# LDS5362BS_breakout.net
KiCad netlist of a schematic drawn in EAGLE
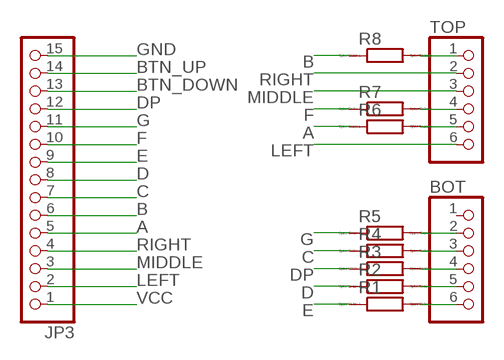
[diagram p0: schematic, sheet 1]

(export (version "E")
  (design (tool "Eeschema 10.0.6"))
  (components
    (comp (ref "BOT")
      (value "PINHD-1X6")
      (footprint "eagle-import:1X06")
      (libsource (lib "eagle-import") (part "PINHD-1X6"))
    )
    (comp (ref "JP3")
      (value "PINHD-1X15")
      (footprint "eagle-import:1X15")
      (libsource (lib "eagle-import") (part "PINHD-1X15"))
    )
    (comp (ref "R1")
      (value "R-EU_R1206")
      (footprint "eagle-import:R1206")
      (libsource (lib "eagle-import") (part "R-EU_R1206"))
    )
    (comp (ref "R2")
      (value "R-EU_R1206")
      (footprint "eagle-import:R1206")
      (libsource (lib "eagle-import") (part "R-EU_R1206"))
    )
    (comp (ref "R3")
      (value "R-EU_R1206")
      (footprint "eagle-import:R1206")
      (libsource (lib "eagle-import") (part "R-EU_R1206"))
    )
    (comp (ref "R4")
      (value "R-EU_R1206")
      (footprint "eagle-import:R1206")
      (libsource (lib "eagle-import") (part "R-EU_R1206"))
    )
    (comp (ref "R5")
      (value "R-EU_R1206")
      (footprint "eagle-import:R1206")
      (libsource (lib "eagle-import") (part "R-EU_R1206"))
    )
    (comp (ref "R6")
      (value "R-EU_R1206")
      (footprint "eagle-import:R1206")
      (libsource (lib "eagle-import") (part "R-EU_R1206"))
    )
    (comp (ref "R7")
      (value "R-EU_R1206")
      (footprint "eagle-import:R1206")
      (libsource (lib "eagle-import") (part "R-EU_R1206"))
    )
    (comp (ref "R8")
      (value "R-EU_R1206")
      (footprint "eagle-import:R1206")
      (libsource (lib "eagle-import") (part "R-EU_R1206"))
    )
    (comp (ref "TOP")
      (value "PINHD-1X6")
      (footprint "eagle-import:1X06")
      (libsource (lib "eagle-import") (part "PINHD-1X6"))
    )
  )
  (nets
    (net (code "1") (name "/A") (class "Default")
      (node (ref "JP3") (pin "5") (pinfunction "5_5") (pintype "passive"))
      (node (ref "R6") (pin "1") (pinfunction "1_1") (pintype "passive"))
    )
    (net (code "2") (name "/B") (class "Default")
      (node (ref "JP3") (pin "6") (pinfunction "6_6") (pintype "passive"))
      (node (ref "R8") (pin "1") (pinfunction "1_1") (pintype "passive"))
    )
    (net (code "3") (name "/BTN_DOWN") (class "Default")
      (node (ref "JP3") (pin "13") (pinfunction "13_13") (pintype "passive"))
    )
    (net (code "4") (name "/BTN_UP") (class "Default")
      (node (ref "JP3") (pin "14") (pinfunction "14_14") (pintype "passive"))
    )
    (net (code "5") (name "/C") (class "Default")
      (node (ref "JP3") (pin "7") (pinfunction "7_7") (pintype "passive"))
      (node (ref "R4") (pin "1") (pinfunction "1_1") (pintype "passive"))
    )
    (net (code "6") (name "/D") (class "Default")
      (node (ref "JP3") (pin "8") (pinfunction "8_8") (pintype "passive"))
      (node (ref "R2") (pin "1") (pinfunction "1_1") (pintype "passive"))
    )
    (net (code "7") (name "/DP") (class "Default")
      (node (ref "JP3") (pin "12") (pinfunction "12_12") (pintype "passive"))
      (node (ref "R3") (pin "1") (pinfunction "1_1") (pintype "passive"))
    )
    (net (code "8") (name "/E") (class "Default")
      (node (ref "JP3") (pin "9") (pinfunction "9_9") (pintype "passive"))
      (node (ref "R1") (pin "1") (pinfunction "1_1") (pintype "passive"))
    )
    (net (code "9") (name "/F") (class "Default")
      (node (ref "JP3") (pin "10") (pinfunction "10_10") (pintype "passive"))
      (node (ref "R7") (pin "1") (pinfunction "1_1") (pintype "passive"))
    )
    (net (code "10") (name "/G") (class "Default")
      (node (ref "JP3") (pin "11") (pinfunction "11_11") (pintype "passive"))
      (node (ref "R5") (pin "1") (pinfunction "1_1") (pintype "passive"))
    )
    (net (code "11") (name "/GND") (class "Default")
      (node (ref "JP3") (pin "15") (pinfunction "15_15") (pintype "passive"))
    )
    (net (code "12") (name "/LEFT") (class "Default")
      (node (ref "JP3") (pin "2") (pinfunction "2_2") (pintype "passive"))
      (node (ref "TOP") (pin "6") (pinfunction "6_6") (pintype "passive"))
    )
    (net (code "13") (name "/MIDDLE") (class "Default")
      (node (ref "JP3") (pin "3") (pinfunction "3_3") (pintype "passive"))
      (node (ref "TOP") (pin "3") (pinfunction "3_3") (pintype "passive"))
    )
    (net (code "14") (name "/RIGHT") (class "Default")
      (node (ref "JP3") (pin "4") (pinfunction "4_4") (pintype "passive"))
      (node (ref "TOP") (pin "2") (pinfunction "2_2") (pintype "passive"))
    )
    (net (code "15") (name "/VCC") (class "Default")
      (node (ref "JP3") (pin "1") (pinfunction "1_1") (pintype "passive"))
    )
    (net (code "16") (name "Net-(BOT-Pad2)") (class "Default")
      (node (ref "BOT") (pin "2") (pinfunction "2_2") (pintype "passive"))
      (node (ref "R5") (pin "2") (pinfunction "2_2") (pintype "passive"))
    )
    (net (code "17") (name "Net-(BOT-Pad3)") (class "Default")
      (node (ref "BOT") (pin "3") (pinfunction "3_3") (pintype "passive"))
      (node (ref "R4") (pin "2") (pinfunction "2_2") (pintype "passive"))
    )
    (net (code "18") (name "Net-(BOT-Pad4)") (class "Default")
      (node (ref "BOT") (pin "4") (pinfunction "4_4") (pintype "passive"))
      (node (ref "R3") (pin "2") (pinfunction "2_2") (pintype "passive"))
    )
    (net (code "19") (name "Net-(BOT-Pad5)") (class "Default")
      (node (ref "BOT") (pin "5") (pinfunction "5_5") (pintype "passive"))
      (node (ref "R2") (pin "2") (pinfunction "2_2") (pintype "passive"))
    )
    (net (code "20") (name "Net-(BOT-Pad6)") (class "Default")
      (node (ref "BOT") (pin "6") (pinfunction "6_6") (pintype "passive"))
      (node (ref "R1") (pin "2") (pinfunction "2_2") (pintype "passive"))
    )
    (net (code "21") (name "Net-(R6-Pad2)") (class "Default")
      (node (ref "R6") (pin "2") (pinfunction "2_2") (pintype "passive"))
      (node (ref "TOP") (pin "5") (pinfunction "5_5") (pintype "passive"))
    )
    (net (code "22") (name "Net-(R7-Pad2)") (class "Default")
      (node (ref "R7") (pin "2") (pinfunction "2_2") (pintype "passive"))
      (node (ref "TOP") (pin "4") (pinfunction "4_4") (pintype "passive"))
    )
    (net (code "23") (name "Net-(R8-Pad2)") (class "Default")
      (node (ref "R8") (pin "2") (pinfunction "2_2") (pintype "passive"))
      (node (ref "TOP") (pin "1") (pinfunction "1_1") (pintype "passive"))
    )
    (net (code "24") (name "unconnected-(BOT-Pad1)") (class "Default")
      (node (ref "BOT") (pin "1") (pinfunction "1_1") (pintype "passive"))
    )
  )
)
